# PC03.net
KiCad netlist of a schematic drawn in EAGLE
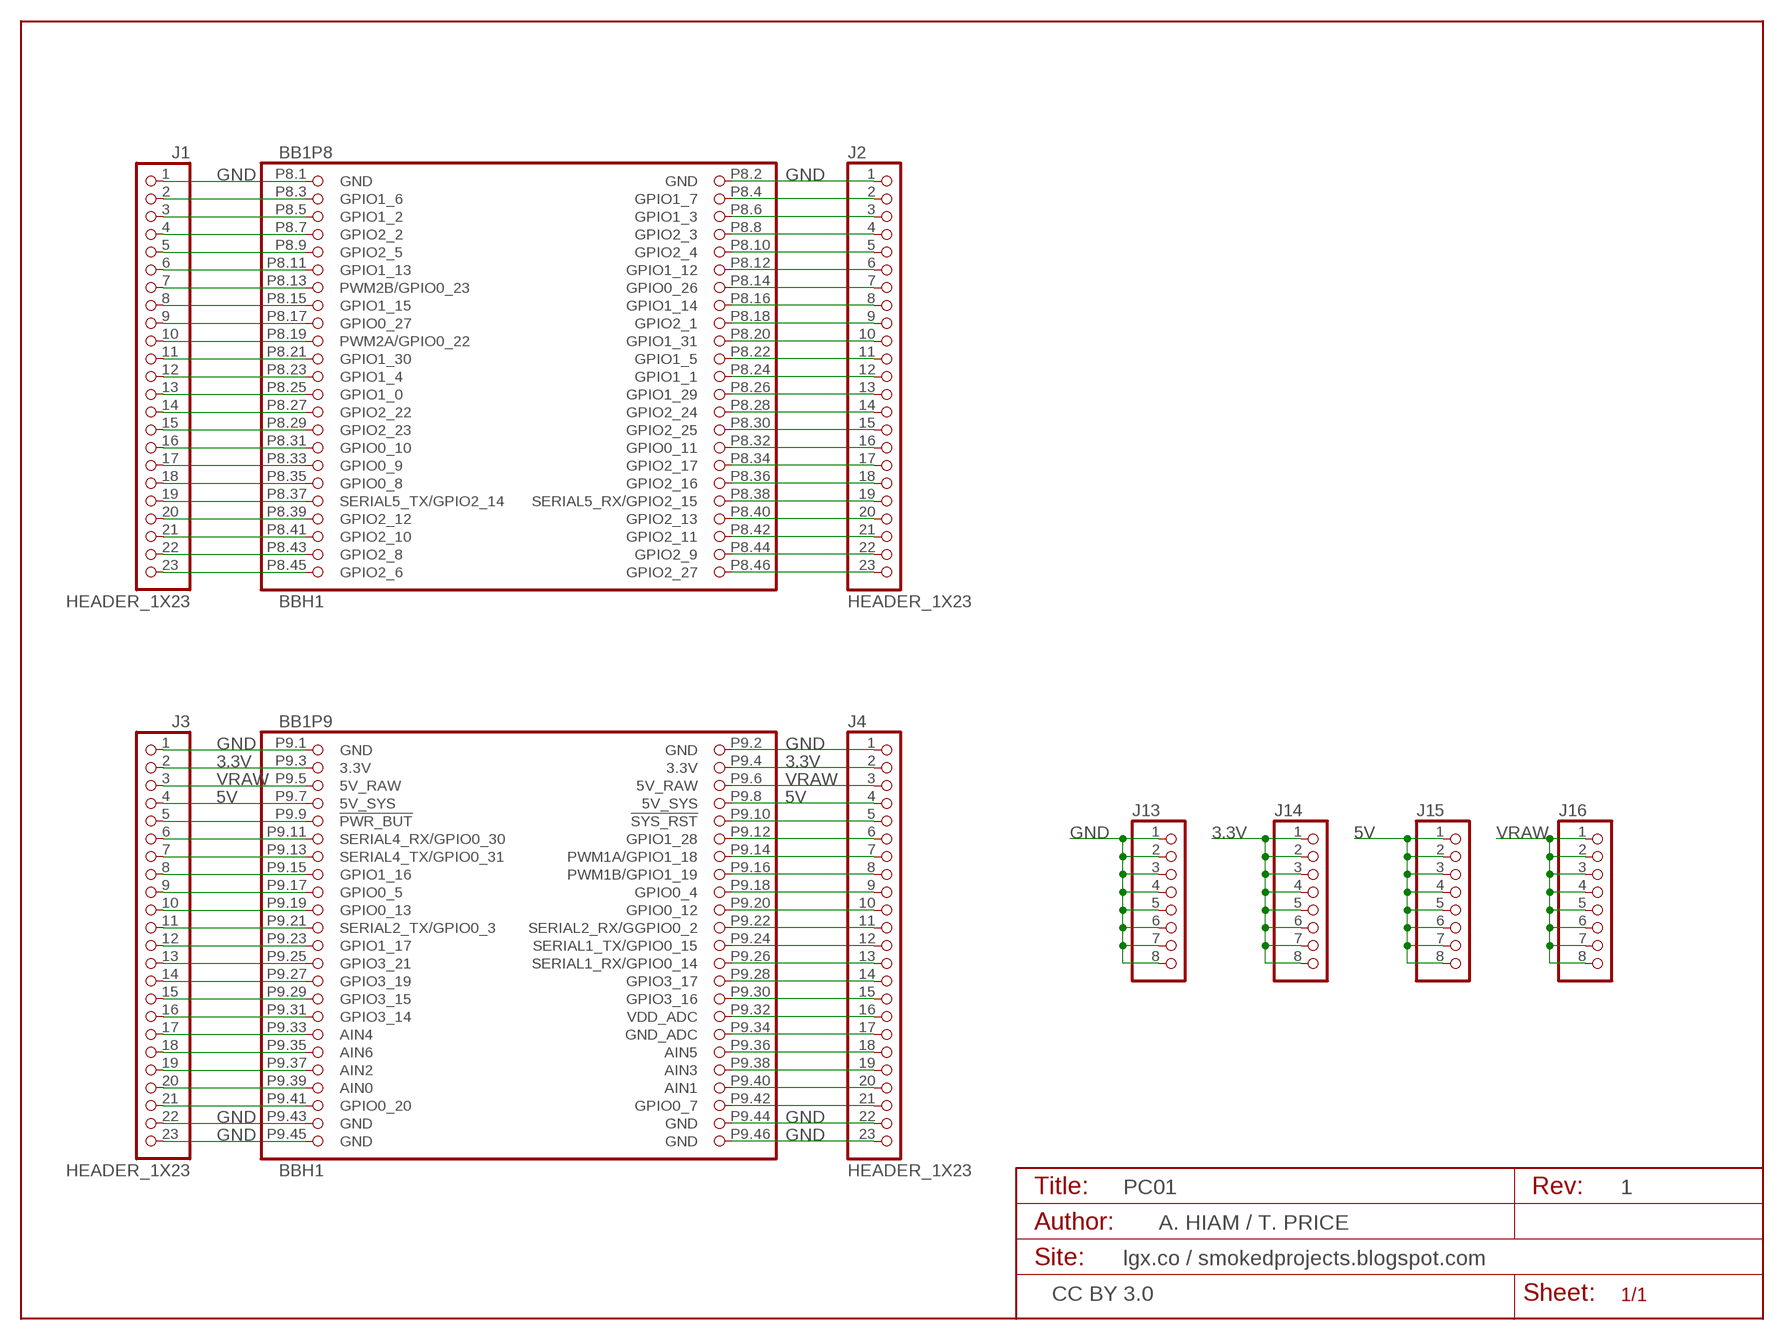
[diagram p0: schematic, sheet 1]

(export (version "E")
  (design (tool "Eeschema 10.0.6"))
  (components
    (comp (ref "BB1")
      (value "BBH1")
      (footprint "eagle-import:BB_CAPE")
      (libsource (lib "eagle-import") (part "BBH1"))
    )
    (comp (ref "J1")
      (value "HEADER_1X23")
      (footprint "eagle-import:HEADER_1X23")
      (libsource (lib "eagle-import") (part "HEADER_1X23"))
    )
    (comp (ref "J2")
      (value "HEADER_1X23")
      (footprint "eagle-import:HEADER_1X23")
      (libsource (lib "eagle-import") (part "HEADER_1X23"))
    )
    (comp (ref "J3")
      (value "HEADER_1X23")
      (footprint "eagle-import:HEADER_1X23")
      (libsource (lib "eagle-import") (part "HEADER_1X23"))
    )
    (comp (ref "J4")
      (value "HEADER_1X23")
      (footprint "eagle-import:HEADER_1X23")
      (libsource (lib "eagle-import") (part "HEADER_1X23"))
    )
    (comp (ref "J13")
      (value "HEADER_1X8")
      (footprint "eagle-import:HEADER_1X8")
      (libsource (lib "eagle-import") (part "HEADER_1X8"))
    )
    (comp (ref "J14")
      (value "HEADER_1X8")
      (footprint "eagle-import:HEADER_1X8")
      (libsource (lib "eagle-import") (part "HEADER_1X8"))
    )
    (comp (ref "J15")
      (value "HEADER_1X8")
      (footprint "eagle-import:HEADER_1X8")
      (libsource (lib "eagle-import") (part "HEADER_1X8"))
    )
    (comp (ref "J16")
      (value "HEADER_1X8")
      (footprint "eagle-import:HEADER_1X8")
      (libsource (lib "eagle-import") (part "HEADER_1X8"))
    )
  )
  (nets
    (net (code "1") (name "/3.3V") (class "Default")
      (node (ref "BB1") (pin "P9.3") (pinfunction "3.3V_P9.3") (pintype "power_in"))
      (node (ref "BB1") (pin "P9.4") (pinfunction "3.3V_P9.4") (pintype "power_in"))
      (node (ref "J14") (pin "1") (pinfunction "1_1") (pintype "passive"))
      (node (ref "J14") (pin "2") (pinfunction "2_2") (pintype "passive"))
      (node (ref "J14") (pin "3") (pinfunction "3_3") (pintype "passive"))
      (node (ref "J14") (pin "4") (pinfunction "4_4") (pintype "passive"))
      (node (ref "J14") (pin "5") (pinfunction "5_5") (pintype "passive"))
      (node (ref "J14") (pin "6") (pinfunction "6_6") (pintype "passive"))
      (node (ref "J14") (pin "7") (pinfunction "7_7") (pintype "passive"))
      (node (ref "J14") (pin "8") (pinfunction "8_8") (pintype "passive"))
      (node (ref "J3") (pin "2") (pinfunction "2_2") (pintype "passive"))
      (node (ref "J4") (pin "2") (pinfunction "2_2") (pintype "passive"))
    )
    (net (code "2") (name "/5V") (class "Default")
      (node (ref "BB1") (pin "P9.7") (pinfunction "5V_SYS_P9.7") (pintype "power_in"))
      (node (ref "BB1") (pin "P9.8") (pinfunction "5V_SYS_P9.8") (pintype "power_in"))
      (node (ref "J15") (pin "1") (pinfunction "1_1") (pintype "passive"))
      (node (ref "J15") (pin "2") (pinfunction "2_2") (pintype "passive"))
      (node (ref "J15") (pin "3") (pinfunction "3_3") (pintype "passive"))
      (node (ref "J15") (pin "4") (pinfunction "4_4") (pintype "passive"))
      (node (ref "J15") (pin "5") (pinfunction "5_5") (pintype "passive"))
      (node (ref "J15") (pin "6") (pinfunction "6_6") (pintype "passive"))
      (node (ref "J15") (pin "7") (pinfunction "7_7") (pintype "passive"))
      (node (ref "J15") (pin "8") (pinfunction "8_8") (pintype "passive"))
      (node (ref "J3") (pin "4") (pinfunction "4_4") (pintype "passive"))
      (node (ref "J4") (pin "4") (pinfunction "4_4") (pintype "passive"))
    )
    (net (code "3") (name "/GND") (class "Default")
      (node (ref "BB1") (pin "P8.1") (pinfunction "GND_P8.1") (pintype "power_in"))
      (node (ref "BB1") (pin "P8.2") (pinfunction "GND_P8.2") (pintype "power_in"))
      (node (ref "BB1") (pin "P9.1") (pinfunction "GND_P9.1") (pintype "power_in"))
      (node (ref "BB1") (pin "P9.2") (pinfunction "GND_P9.2") (pintype "power_in"))
      (node (ref "BB1") (pin "P9.43") (pinfunction "GND_P9.43") (pintype "bidirectional"))
      (node (ref "BB1") (pin "P9.44") (pinfunction "GND_P9.44") (pintype "bidirectional"))
      (node (ref "BB1") (pin "P9.45") (pinfunction "GND_P9.45") (pintype "bidirectional"))
      (node (ref "BB1") (pin "P9.46") (pinfunction "GND_P9.46") (pintype "bidirectional"))
      (node (ref "J1") (pin "1") (pinfunction "1_1") (pintype "passive"))
      (node (ref "J13") (pin "1") (pinfunction "1_1") (pintype "passive"))
      (node (ref "J13") (pin "2") (pinfunction "2_2") (pintype "passive"))
      (node (ref "J13") (pin "3") (pinfunction "3_3") (pintype "passive"))
      (node (ref "J13") (pin "4") (pinfunction "4_4") (pintype "passive"))
      (node (ref "J13") (pin "5") (pinfunction "5_5") (pintype "passive"))
      (node (ref "J13") (pin "6") (pinfunction "6_6") (pintype "passive"))
      (node (ref "J13") (pin "7") (pinfunction "7_7") (pintype "passive"))
      (node (ref "J13") (pin "8") (pinfunction "8_8") (pintype "passive"))
      (node (ref "J2") (pin "1") (pinfunction "1_1") (pintype "passive"))
      (node (ref "J3") (pin "1") (pinfunction "1_1") (pintype "passive"))
      (node (ref "J3") (pin "22") (pinfunction "22_22") (pintype "passive"))
      (node (ref "J3") (pin "23") (pinfunction "23_23") (pintype "passive"))
      (node (ref "J4") (pin "1") (pinfunction "1_1") (pintype "passive"))
      (node (ref "J4") (pin "22") (pinfunction "22_22") (pintype "passive"))
      (node (ref "J4") (pin "23") (pinfunction "23_23") (pintype "passive"))
    )
    (net (code "4") (name "/VRAW") (class "Default")
      (node (ref "BB1") (pin "P9.5") (pinfunction "5V_RAW_P9.5") (pintype "power_in"))
      (node (ref "BB1") (pin "P9.6") (pinfunction "5V_RAW_P9.6") (pintype "power_in"))
      (node (ref "J16") (pin "1") (pinfunction "1_1") (pintype "passive"))
      (node (ref "J16") (pin "2") (pinfunction "2_2") (pintype "passive"))
      (node (ref "J16") (pin "3") (pinfunction "3_3") (pintype "passive"))
      (node (ref "J16") (pin "4") (pinfunction "4_4") (pintype "passive"))
      (node (ref "J16") (pin "5") (pinfunction "5_5") (pintype "passive"))
      (node (ref "J16") (pin "6") (pinfunction "6_6") (pintype "passive"))
      (node (ref "J16") (pin "7") (pinfunction "7_7") (pintype "passive"))
      (node (ref "J16") (pin "8") (pinfunction "8_8") (pintype "passive"))
      (node (ref "J3") (pin "3") (pinfunction "3_3") (pintype "passive"))
      (node (ref "J4") (pin "3") (pinfunction "3_3") (pintype "passive"))
    )
    (net (code "5") (name "Net-(BB1A-GPIO0_8)") (class "Default")
      (node (ref "BB1") (pin "P8.35") (pinfunction "GPIO0_8_P8.35") (pintype "bidirectional"))
      (node (ref "J1") (pin "18") (pinfunction "18_18") (pintype "passive"))
    )
    (net (code "6") (name "Net-(BB1A-GPIO0_9)") (class "Default")
      (node (ref "BB1") (pin "P8.33") (pinfunction "GPIO0_9_P8.33") (pintype "bidirectional"))
      (node (ref "J1") (pin "17") (pinfunction "17_17") (pintype "passive"))
    )
    (net (code "7") (name "Net-(BB1A-GPIO0_10)") (class "Default")
      (node (ref "BB1") (pin "P8.31") (pinfunction "GPIO0_10_P8.31") (pintype "bidirectional"))
      (node (ref "J1") (pin "16") (pinfunction "16_16") (pintype "passive"))
    )
    (net (code "8") (name "Net-(BB1A-GPIO0_11)") (class "Default")
      (node (ref "BB1") (pin "P8.32") (pinfunction "GPIO0_11_P8.32") (pintype "bidirectional"))
      (node (ref "J2") (pin "16") (pinfunction "16_16") (pintype "passive"))
    )
    (net (code "9") (name "Net-(BB1A-GPIO0_26)") (class "Default")
      (node (ref "BB1") (pin "P8.14") (pinfunction "GPIO0_26_P8.14") (pintype "bidirectional"))
      (node (ref "J2") (pin "7") (pinfunction "7_7") (pintype "passive"))
    )
    (net (code "10") (name "Net-(BB1A-GPIO0_27)") (class "Default")
      (node (ref "BB1") (pin "P8.17") (pinfunction "GPIO0_27_P8.17") (pintype "bidirectional"))
      (node (ref "J1") (pin "9") (pinfunction "9_9") (pintype "passive"))
    )
    (net (code "11") (name "Net-(BB1A-GPIO1_0)") (class "Default")
      (node (ref "BB1") (pin "P8.25") (pinfunction "GPIO1_0_P8.25") (pintype "bidirectional"))
      (node (ref "J1") (pin "13") (pinfunction "13_13") (pintype "passive"))
    )
    (net (code "12") (name "Net-(BB1A-GPIO1_1)") (class "Default")
      (node (ref "BB1") (pin "P8.24") (pinfunction "GPIO1_1_P8.24") (pintype "bidirectional"))
      (node (ref "J2") (pin "12") (pinfunction "12_12") (pintype "passive"))
    )
    (net (code "13") (name "Net-(BB1A-GPIO1_2)") (class "Default")
      (node (ref "BB1") (pin "P8.5") (pinfunction "GPIO1_2_P8.5") (pintype "bidirectional"))
      (node (ref "J1") (pin "3") (pinfunction "3_3") (pintype "passive"))
    )
    (net (code "14") (name "Net-(BB1A-GPIO1_3)") (class "Default")
      (node (ref "BB1") (pin "P8.6") (pinfunction "GPIO1_3_P8.6") (pintype "bidirectional"))
      (node (ref "J2") (pin "3") (pinfunction "3_3") (pintype "passive"))
    )
    (net (code "15") (name "Net-(BB1A-GPIO1_4)") (class "Default")
      (node (ref "BB1") (pin "P8.23") (pinfunction "GPIO1_4_P8.23") (pintype "bidirectional"))
      (node (ref "J1") (pin "12") (pinfunction "12_12") (pintype "passive"))
    )
    (net (code "16") (name "Net-(BB1A-GPIO1_5)") (class "Default")
      (node (ref "BB1") (pin "P8.22") (pinfunction "GPIO1_5_P8.22") (pintype "bidirectional"))
      (node (ref "J2") (pin "11") (pinfunction "11_11") (pintype "passive"))
    )
    (net (code "17") (name "Net-(BB1A-GPIO1_6)") (class "Default")
      (node (ref "BB1") (pin "P8.3") (pinfunction "GPIO1_6_P8.3") (pintype "bidirectional"))
      (node (ref "J1") (pin "2") (pinfunction "2_2") (pintype "passive"))
    )
    (net (code "18") (name "Net-(BB1A-GPIO1_7)") (class "Default")
      (node (ref "BB1") (pin "P8.4") (pinfunction "GPIO1_7_P8.4") (pintype "bidirectional"))
      (node (ref "J2") (pin "2") (pinfunction "2_2") (pintype "passive"))
    )
    (net (code "19") (name "Net-(BB1A-GPIO1_12)") (class "Default")
      (node (ref "BB1") (pin "P8.12") (pinfunction "GPIO1_12_P8.12") (pintype "bidirectional"))
      (node (ref "J2") (pin "6") (pinfunction "6_6") (pintype "passive"))
    )
    (net (code "20") (name "Net-(BB1A-GPIO1_13)") (class "Default")
      (node (ref "BB1") (pin "P8.11") (pinfunction "GPIO1_13_P8.11") (pintype "bidirectional"))
      (node (ref "J1") (pin "6") (pinfunction "6_6") (pintype "passive"))
    )
    (net (code "21") (name "Net-(BB1A-GPIO1_14)") (class "Default")
      (node (ref "BB1") (pin "P8.16") (pinfunction "GPIO1_14_P8.16") (pintype "bidirectional"))
      (node (ref "J2") (pin "8") (pinfunction "8_8") (pintype "passive"))
    )
    (net (code "22") (name "Net-(BB1A-GPIO1_15)") (class "Default")
      (node (ref "BB1") (pin "P8.15") (pinfunction "GPIO1_15_P8.15") (pintype "bidirectional"))
      (node (ref "J1") (pin "8") (pinfunction "8_8") (pintype "passive"))
    )
    (net (code "23") (name "Net-(BB1A-GPIO1_29)") (class "Default")
      (node (ref "BB1") (pin "P8.26") (pinfunction "GPIO1_29_P8.26") (pintype "bidirectional"))
      (node (ref "J2") (pin "13") (pinfunction "13_13") (pintype "passive"))
    )
    (net (code "24") (name "Net-(BB1A-GPIO1_30)") (class "Default")
      (node (ref "BB1") (pin "P8.21") (pinfunction "GPIO1_30_P8.21") (pintype "bidirectional"))
      (node (ref "J1") (pin "11") (pinfunction "11_11") (pintype "passive"))
    )
    (net (code "25") (name "Net-(BB1A-GPIO1_31)") (class "Default")
      (node (ref "BB1") (pin "P8.20") (pinfunction "GPIO1_31_P8.20") (pintype "bidirectional"))
      (node (ref "J2") (pin "10") (pinfunction "10_10") (pintype "passive"))
    )
    (net (code "26") (name "Net-(BB1A-GPIO2_1)") (class "Default")
      (node (ref "BB1") (pin "P8.18") (pinfunction "GPIO2_1_P8.18") (pintype "bidirectional"))
      (node (ref "J2") (pin "9") (pinfunction "9_9") (pintype "passive"))
    )
    (net (code "27") (name "Net-(BB1A-GPIO2_2)") (class "Default")
      (node (ref "BB1") (pin "P8.7") (pinfunction "GPIO2_2_P8.7") (pintype "bidirectional"))
      (node (ref "J1") (pin "4") (pinfunction "4_4") (pintype "passive"))
    )
    (net (code "28") (name "Net-(BB1A-GPIO2_3)") (class "Default")
      (node (ref "BB1") (pin "P8.8") (pinfunction "GPIO2_3_P8.8") (pintype "bidirectional"))
      (node (ref "J2") (pin "4") (pinfunction "4_4") (pintype "passive"))
    )
    (net (code "29") (name "Net-(BB1A-GPIO2_4)") (class "Default")
      (node (ref "BB1") (pin "P8.10") (pinfunction "GPIO2_4_P8.10") (pintype "bidirectional"))
      (node (ref "J2") (pin "5") (pinfunction "5_5") (pintype "passive"))
    )
    (net (code "30") (name "Net-(BB1A-GPIO2_5)") (class "Default")
      (node (ref "BB1") (pin "P8.9") (pinfunction "GPIO2_5_P8.9") (pintype "bidirectional"))
      (node (ref "J1") (pin "5") (pinfunction "5_5") (pintype "passive"))
    )
    (net (code "31") (name "Net-(BB1A-GPIO2_6)") (class "Default")
      (node (ref "BB1") (pin "P8.45") (pinfunction "GPIO2_6_P8.45") (pintype "bidirectional"))
      (node (ref "J1") (pin "23") (pinfunction "23_23") (pintype "passive"))
    )
    (net (code "32") (name "Net-(BB1A-GPIO2_8)") (class "Default")
      (node (ref "BB1") (pin "P8.43") (pinfunction "GPIO2_8_P8.43") (pintype "bidirectional"))
      (node (ref "J1") (pin "22") (pinfunction "22_22") (pintype "passive"))
    )
    (net (code "33") (name "Net-(BB1A-GPIO2_9)") (class "Default")
      (node (ref "BB1") (pin "P8.44") (pinfunction "GPIO2_9_P8.44") (pintype "bidirectional"))
      (node (ref "J2") (pin "22") (pinfunction "22_22") (pintype "passive"))
    )
    (net (code "34") (name "Net-(BB1A-GPIO2_10)") (class "Default")
      (node (ref "BB1") (pin "P8.41") (pinfunction "GPIO2_10_P8.41") (pintype "bidirectional"))
      (node (ref "J1") (pin "21") (pinfunction "21_21") (pintype "passive"))
    )
    (net (code "35") (name "Net-(BB1A-GPIO2_11)") (class "Default")
      (node (ref "BB1") (pin "P8.42") (pinfunction "GPIO2_11_P8.42") (pintype "bidirectional"))
      (node (ref "J2") (pin "21") (pinfunction "21_21") (pintype "passive"))
    )
    (net (code "36") (name "Net-(BB1A-GPIO2_12)") (class "Default")
      (node (ref "BB1") (pin "P8.39") (pinfunction "GPIO2_12_P8.39") (pintype "bidirectional"))
      (node (ref "J1") (pin "20") (pinfunction "20_20") (pintype "passive"))
    )
    (net (code "37") (name "Net-(BB1A-GPIO2_13)") (class "Default")
      (node (ref "BB1") (pin "P8.40") (pinfunction "GPIO2_13_P8.40") (pintype "bidirectional"))
      (node (ref "J2") (pin "20") (pinfunction "20_20") (pintype "passive"))
    )
    (net (code "38") (name "Net-(BB1A-GPIO2_16)") (class "Default")
      (node (ref "BB1") (pin "P8.36") (pinfunction "GPIO2_16_P8.36") (pintype "bidirectional"))
      (node (ref "J2") (pin "18") (pinfunction "18_18") (pintype "passive"))
    )
    (net (code "39") (name "Net-(BB1A-GPIO2_17)") (class "Default")
      (node (ref "BB1") (pin "P8.34") (pinfunction "GPIO2_17_P8.34") (pintype "bidirectional"))
      (node (ref "J2") (pin "17") (pinfunction "17_17") (pintype "passive"))
    )
    (net (code "40") (name "Net-(BB1A-GPIO2_22)") (class "Default")
      (node (ref "BB1") (pin "P8.27") (pinfunction "GPIO2_22_P8.27") (pintype "bidirectional"))
      (node (ref "J1") (pin "14") (pinfunction "14_14") (pintype "passive"))
    )
    (net (code "41") (name "Net-(BB1A-GPIO2_23)") (class "Default")
      (node (ref "BB1") (pin "P8.29") (pinfunction "GPIO2_23_P8.29") (pintype "bidirectional"))
      (node (ref "J1") (pin "15") (pinfunction "15_15") (pintype "passive"))
    )
    (net (code "42") (name "Net-(BB1A-GPIO2_24)") (class "Default")
      (node (ref "BB1") (pin "P8.28") (pinfunction "GPIO2_24_P8.28") (pintype "bidirectional"))
      (node (ref "J2") (pin "14") (pinfunction "14_14") (pintype "passive"))
    )
    (net (code "43") (name "Net-(BB1A-GPIO2_25)") (class "Default")
      (node (ref "BB1") (pin "P8.30") (pinfunction "GPIO2_25_P8.30") (pintype "bidirectional"))
      (node (ref "J2") (pin "15") (pinfunction "15_15") (pintype "passive"))
    )
    (net (code "44") (name "Net-(BB1A-GPIO2_27)") (class "Default")
      (node (ref "BB1") (pin "P8.46") (pinfunction "GPIO2_27_P8.46") (pintype "bidirectional"))
      (node (ref "J2") (pin "23") (pinfunction "23_23") (pintype "passive"))
    )
    (net (code "45") (name "Net-(BB1A-PWM2A{slash}GPIO0_22)") (class "Default")
      (node (ref "BB1") (pin "P8.19") (pinfunction "PWM2A/GPIO0_22_P8.19") (pintype "bidirectional"))
      (node (ref "J1") (pin "10") (pinfunction "10_10") (pintype "passive"))
    )
    (net (code "46") (name "Net-(BB1A-PWM2B{slash}GPIO0_23)") (class "Default")
      (node (ref "BB1") (pin "P8.13") (pinfunction "PWM2B/GPIO0_23_P8.13") (pintype "bidirectional"))
      (node (ref "J1") (pin "7") (pinfunction "7_7") (pintype "passive"))
    )
    (net (code "47") (name "Net-(BB1A-SERIAL5_RX{slash}GPIO2_15)") (class "Default")
      (node (ref "BB1") (pin "P8.38") (pinfunction "SERIAL5_RX/GPIO2_15_P8.38") (pintype "bidirectional"))
      (node (ref "J2") (pin "19") (pinfunction "19_19") (pintype "passive"))
    )
    (net (code "48") (name "Net-(BB1A-SERIAL5_TX{slash}GPIO2_14)") (class "Default")
      (node (ref "BB1") (pin "P8.37") (pinfunction "SERIAL5_TX/GPIO2_14_P8.37") (pintype "bidirectional"))
      (node (ref "J1") (pin "19") (pinfunction "19_19") (pintype "passive"))
    )
    (net (code "49") (name "Net-(BB1B-AIN0)") (class "Default")
      (node (ref "BB1") (pin "P9.39") (pinfunction "AIN0_P9.39") (pintype "input"))
      (node (ref "J3") (pin "20") (pinfunction "20_20") (pintype "passive"))
    )
    (net (code "50") (name "Net-(BB1B-AIN1)") (class "Default")
      (node (ref "BB1") (pin "P9.40") (pinfunction "AIN1_P9.40") (pintype "input"))
      (node (ref "J4") (pin "20") (pinfunction "20_20") (pintype "passive"))
    )
    (net (code "51") (name "Net-(BB1B-AIN2)") (class "Default")
      (node (ref "BB1") (pin "P9.37") (pinfunction "AIN2_P9.37") (pintype "input"))
      (node (ref "J3") (pin "19") (pinfunction "19_19") (pintype "passive"))
    )
    (net (code "52") (name "Net-(BB1B-AIN3)") (class "Default")
      (node (ref "BB1") (pin "P9.38") (pinfunction "AIN3_P9.38") (pintype "input"))
      (node (ref "J4") (pin "19") (pinfunction "19_19") (pintype "passive"))
    )
    (net (code "53") (name "Net-(BB1B-AIN4)") (class "Default")
      (node (ref "BB1") (pin "P9.33") (pinfunction "AIN4_P9.33") (pintype "input"))
      (node (ref "J3") (pin "17") (pinfunction "17_17") (pintype "passive"))
    )
    (net (code "54") (name "Net-(BB1B-AIN5)") (class "Default")
      (node (ref "BB1") (pin "P9.36") (pinfunction "AIN5_P9.36") (pintype "input"))
      (node (ref "J4") (pin "18") (pinfunction "18_18") (pintype "passive"))
    )
    (net (code "55") (name "Net-(BB1B-AIN6)") (class "Default")
      (node (ref "BB1") (pin "P9.35") (pinfunction "AIN6_P9.35") (pintype "input"))
      (node (ref "J3") (pin "18") (pinfunction "18_18") (pintype "passive"))
    )
    (net (code "56") (name "Net-(BB1B-GND_ADC)") (class "Default")
      (node (ref "BB1") (pin "P9.34") (pinfunction "GND_ADC_P9.34") (pintype "bidirectional"))
      (node (ref "J4") (pin "17") (pinfunction "17_17") (pintype "passive"))
    )
    (net (code "57") (name "Net-(BB1B-GPIO0_4)") (class "Default")
      (node (ref "BB1") (pin "P9.18") (pinfunction "GPIO0_4_P9.18") (pintype "bidirectional"))
      (node (ref "J4") (pin "9") (pinfunction "9_9") (pintype "passive"))
    )
    (net (code "58") (name "Net-(BB1B-GPIO0_5)") (class "Default")
      (node (ref "BB1") (pin "P9.17") (pinfunction "GPIO0_5_P9.17") (pintype "bidirectional"))
      (node (ref "J3") (pin "9") (pinfunction "9_9") (pintype "passive"))
    )
    (net (code "59") (name "Net-(BB1B-GPIO0_7)") (class "Default")
      (node (ref "BB1") (pin "P9.42") (pinfunction "GPIO0_7_P9.42") (pintype "bidirectional"))
      (node (ref "J4") (pin "21") (pinfunction "21_21") (pintype "passive"))
    )
    (net (code "60") (name "Net-(BB1B-GPIO0_12)") (class "Default")
      (node (ref "BB1") (pin "P9.20") (pinfunction "GPIO0_12_P9.20") (pintype "bidirectional"))
      (node (ref "J4") (pin "10") (pinfunction "10_10") (pintype "passive"))
    )
    (net (code "61") (name "Net-(BB1B-GPIO0_13)") (class "Default")
      (node (ref "BB1") (pin "P9.19") (pinfunction "GPIO0_13_P9.19") (pintype "bidirectional"))
      (node (ref "J3") (pin "10") (pinfunction "10_10") (pintype "passive"))
    )
    (net (code "62") (name "Net-(BB1B-GPIO0_20)") (class "Default")
      (node (ref "BB1") (pin "P9.41") (pinfunction "GPIO0_20_P9.41") (pintype "bidirectional"))
      (node (ref "J3") (pin "21") (pinfunction "21_21") (pintype "passive"))
    )
    (net (code "63") (name "Net-(BB1B-GPIO1_16)") (class "Default")
      (node (ref "BB1") (pin "P9.15") (pinfunction "GPIO1_16_P9.15") (pintype "bidirectional"))
      (node (ref "J3") (pin "8") (pinfunction "8_8") (pintype "passive"))
    )
    (net (code "64") (name "Net-(BB1B-GPIO1_17)") (class "Default")
      (node (ref "BB1") (pin "P9.23") (pinfunction "GPIO1_17_P9.23") (pintype "bidirectional"))
      (node (ref "J3") (pin "12") (pinfunction "12_12") (pintype "passive"))
    )
    (net (code "65") (name "Net-(BB1B-GPIO1_28)") (class "Default")
      (node (ref "BB1") (pin "P9.12") (pinfunction "GPIO1_28_P9.12") (pintype "bidirectional"))
      (node (ref "J4") (pin "6") (pinfunction "6_6") (pintype "passive"))
    )
    (net (code "66") (name "Net-(BB1B-GPIO3_14)") (class "Default")
      (node (ref "BB1") (pin "P9.31") (pinfunction "GPIO3_14_P9.31") (pintype "bidirectional"))
      (node (ref "J3") (pin "16") (pinfunction "16_16") (pintype "passive"))
    )
    (net (code "67") (name "Net-(BB1B-GPIO3_15)") (class "Default")
      (node (ref "BB1") (pin "P9.29") (pinfunction "GPIO3_15_P9.29") (pintype "bidirectional"))
      (node (ref "J3") (pin "15") (pinfunction "15_15") (pintype "passive"))
    )
    (net (code "68") (name "Net-(BB1B-GPIO3_16)") (class "Default")
      (node (ref "BB1") (pin "P9.30") (pinfunction "GPIO3_16_P9.30") (pintype "bidirectional"))
      (node (ref "J4") (pin "15") (pinfunction "15_15") (pintype "passive"))
    )
    (net (code "69") (name "Net-(BB1B-GPIO3_17)") (class "Default")
      (node (ref "BB1") (pin "P9.28") (pinfunction "GPIO3_17_P9.28") (pintype "bidirectional"))
      (node (ref "J4") (pin "14") (pinfunction "14_14") (pintype "passive"))
    )
    (net (code "70") (name "Net-(BB1B-GPIO3_19)") (class "Default")
      (node (ref "BB1") (pin "P9.27") (pinfunction "GPIO3_19_P9.27") (pintype "bidirectional"))
      (node (ref "J3") (pin "14") (pinfunction "14_14") (pintype "passive"))
    )
    (net (code "71") (name "Net-(BB1B-GPIO3_21)") (class "Default")
      (node (ref "BB1") (pin "P9.25") (pinfunction "GPIO3_21_P9.25") (pintype "bidirectional"))
      (node (ref "J3") (pin "13") (pinfunction "13_13") (pintype "passive"))
    )
    (net (code "72") (name "Net-(BB1B-PWM1A{slash}GPIO1_18)") (class "Default")
      (node (ref "BB1") (pin "P9.14") (pinfunction "PWM1A/GPIO1_18_P9.14") (pintype "bidirectional"))
      (node (ref "J4") (pin "7") (pinfunction "7_7") (pintype "passive"))
    )
    (net (code "73") (name "Net-(BB1B-PWM1B{slash}GPIO1_19)") (class "Default")
      (node (ref "BB1") (pin "P9.16") (pinfunction "PWM1B/GPIO1_19_P9.16") (pintype "bidirectional"))
      (node (ref "J4") (pin "8") (pinfunction "8_8") (pintype "passive"))
    )
    (net (code "74") (name "Net-(BB1B-SERIAL1_RX{slash}GPIO0_14)") (class "Default")
      (node (ref "BB1") (pin "P9.26") (pinfunction "SERIAL1_RX/GPIO0_14_P9.26") (pintype "bidirectional"))
      (node (ref "J4") (pin "13") (pinfunction "13_13") (pintype "passive"))
    )
    (net (code "75") (name "Net-(BB1B-SERIAL1_TX{slash}GPIO0_15)") (class "Default")
      (node (ref "BB1") (pin "P9.24") (pinfunction "SERIAL1_TX/GPIO0_15_P9.24") (pintype "bidirectional"))
      (node (ref "J4") (pin "12") (pinfunction "12_12") (pintype "passive"))
    )
    (net (code "76") (name "Net-(BB1B-SERIAL2_RX{slash}GGPIO0_2)") (class "Default")
      (node (ref "BB1") (pin "P9.22") (pinfunction "SERIAL2_RX/GGPIO0_2_P9.22") (pintype "bidirectional"))
      (node (ref "J4") (pin "11") (pinfunction "11_11") (pintype "passive"))
    )
    (net (code "77") (name "Net-(BB1B-SERIAL2_TX{slash}GPIO0_3)") (class "Default")
      (node (ref "BB1") (pin "P9.21") (pinfunction "SERIAL2_TX/GPIO0_3_P9.21") (pintype "bidirectional"))
      (node (ref "J3") (pin "11") (pinfunction "11_11") (pintype "passive"))
    )
    (net (code "78") (name "Net-(BB1B-SERIAL4_RX{slash}GPIO0_30)") (class "Default")
      (node (ref "BB1") (pin "P9.11") (pinfunction "SERIAL4_RX/GPIO0_30_P9.11") (pintype "bidirectional"))
      (node (ref "J3") (pin "6") (pinfunction "6_6") (pintype "passive"))
    )
    (net (code "79") (name "Net-(BB1B-SERIAL4_TX{slash}GPIO0_31)") (class "Default")
      (node (ref "BB1") (pin "P9.13") (pinfunction "SERIAL4_TX/GPIO0_31_P9.13") (pintype "bidirectional"))
      (node (ref "J3") (pin "7") (pinfunction "7_7") (pintype "passive"))
    )
    (net (code "80") (name "Net-(BB1B-VDD_ADC)") (class "Default")
      (node (ref "BB1") (pin "P9.32") (pinfunction "VDD_ADC_P9.32") (pintype "bidirectional"))
      (node (ref "J4") (pin "16") (pinfunction "16_16") (pintype "passive"))
    )
    (net (code "81") (name "Net-(BB1B-~{PWR_BUT})") (class "Default")
      (node (ref "BB1") (pin "P9.9") (pinfunction "~{PWR_BUT}_P9.9") (pintype "input"))
      (node (ref "J3") (pin "5") (pinfunction "5_5") (pintype "passive"))
    )
    (net (code "82") (name "Net-(BB1B-~{SYS_RST})") (class "Default")
      (node (ref "BB1") (pin "P9.10") (pinfunction "~{SYS_RST}_P9.10") (pintype "input"))
      (node (ref "J4") (pin "5") (pinfunction "5_5") (pintype "passive"))
    )
  )
)
